# Power_Supply_board.net
KiCad netlist of a schematic drawn in EAGLE
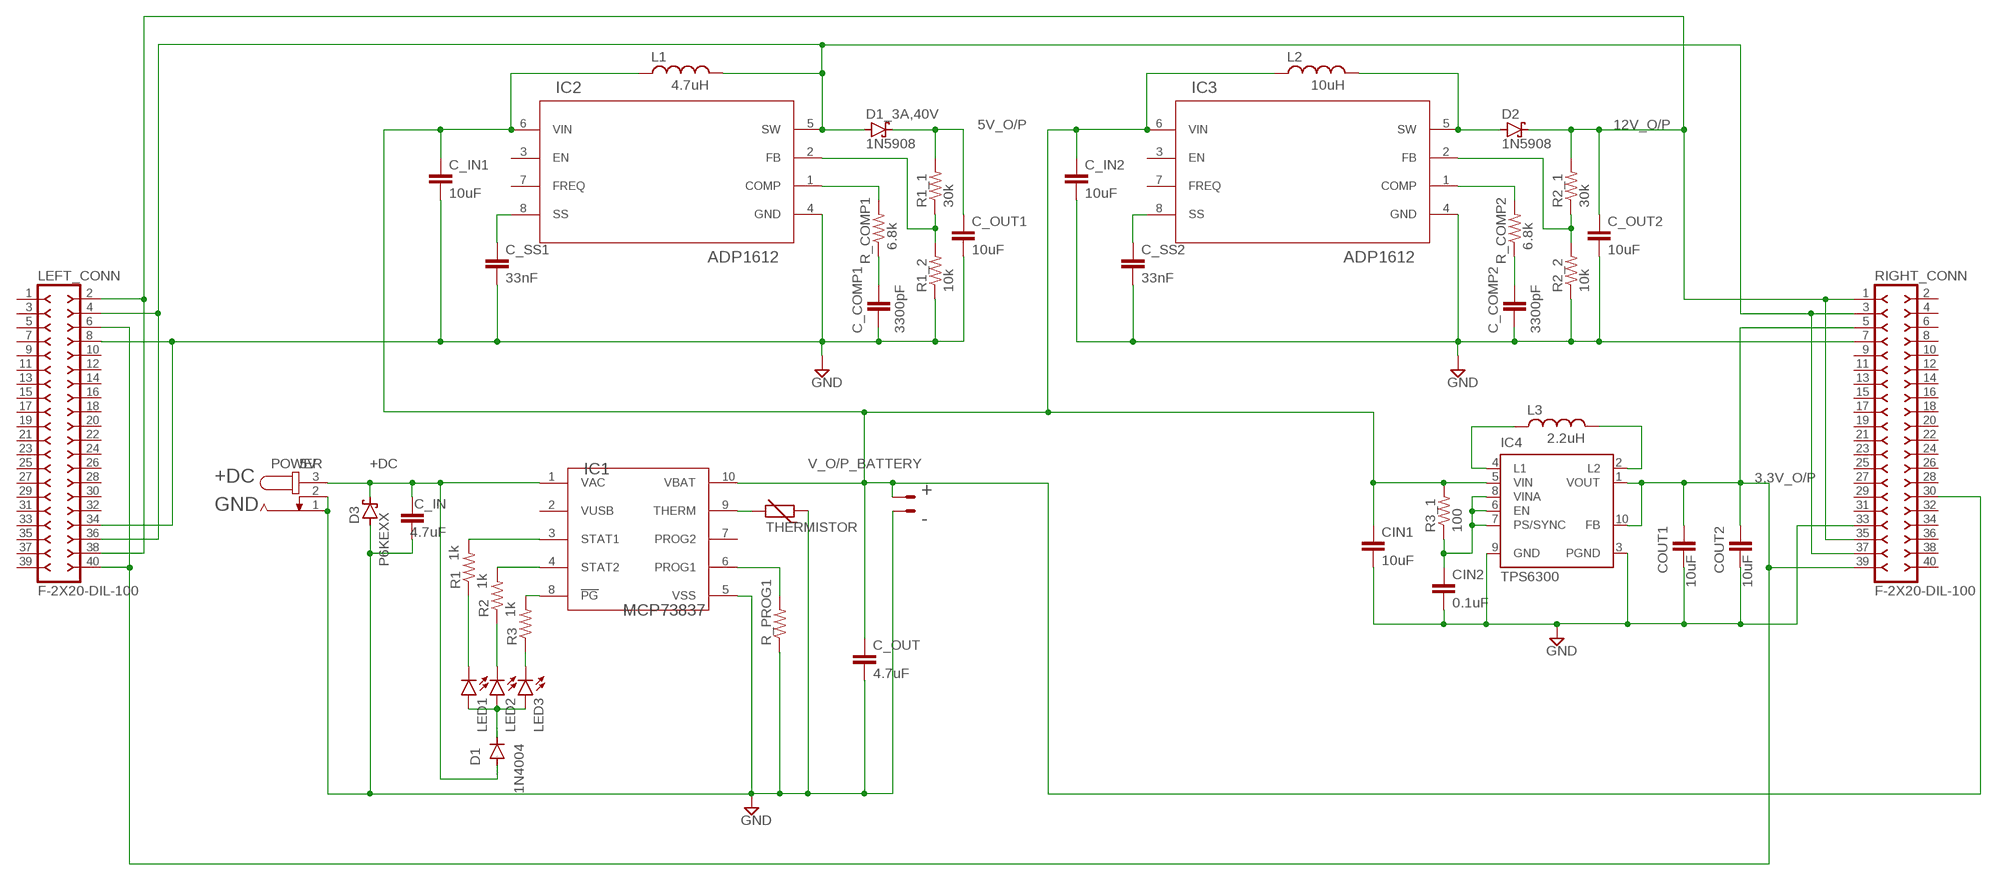
[diagram p0: schematic, sheet 1]

(export (version "E")
  (design (tool "Eeschema 10.0.6"))
  (components
    (comp (ref "BATT-CHARGING")
      (value "JST-XH-02-PIN-ROUND-PAD")
      (footprint "eagle-import:JST-XH-02-PACKAGE-ROUND-PAD")
      (libsource (lib "eagle-import") (part "JST-XH-02-PIN-ROUND-PAD"))
    )
    (comp (ref "CIN1")
      (value "10uF")
      (footprint "eagle-import:C025-024X044")
      (libsource (lib "eagle-import") (part "C-EU025-024X044"))
    )
    (comp (ref "CIN2")
      (value "0.1uF")
      (footprint "eagle-import:C025-024X044")
      (libsource (lib "eagle-import") (part "C-EU025-024X044"))
    )
    (comp (ref "COUT1")
      (value "10uF")
      (footprint "eagle-import:C025-024X044")
      (libsource (lib "eagle-import") (part "C-EU025-024X044"))
    )
    (comp (ref "COUT2")
      (value "10uF")
      (footprint "eagle-import:C025-024X044")
      (libsource (lib "eagle-import") (part "C-EU025-024X044"))
    )
    (comp (ref "C_COMP1")
      (value "3300pF")
      (footprint "eagle-import:C025-024X044")
      (libsource (lib "eagle-import") (part "C-EU025-024X044"))
    )
    (comp (ref "C_COMP2")
      (value "3300pF")
      (footprint "eagle-import:C025-024X044")
      (libsource (lib "eagle-import") (part "C-EU025-024X044"))
    )
    (comp (ref "C_IN")
      (value "4.7uF")
      (footprint "eagle-import:C025-024X044")
      (libsource (lib "eagle-import") (part "C-EU025-024X044"))
    )
    (comp (ref "C_IN1")
      (value "10uF")
      (footprint "eagle-import:C025-024X044")
      (libsource (lib "eagle-import") (part "C-EU025-024X044"))
    )
    (comp (ref "C_IN2")
      (value "10uF")
      (footprint "eagle-import:C025-024X044")
      (libsource (lib "eagle-import") (part "C-EU025-024X044"))
    )
    (comp (ref "C_OUT")
      (value "4.7uF")
      (footprint "eagle-import:C025-024X044")
      (libsource (lib "eagle-import") (part "C-EU025-024X044"))
    )
    (comp (ref "C_OUT1")
      (value "10uF")
      (footprint "eagle-import:C025-024X044")
      (libsource (lib "eagle-import") (part "C-EU025-024X044"))
    )
    (comp (ref "C_OUT2")
      (value "10uF")
      (footprint "eagle-import:C025-024X044")
      (libsource (lib "eagle-import") (part "C-EU025-024X044"))
    )
    (comp (ref "C_SS1")
      (value "33nF")
      (footprint "eagle-import:C025-024X044")
      (libsource (lib "eagle-import") (part "C-EU025-024X044"))
    )
    (comp (ref "C_SS2")
      (value "33nF")
      (footprint "eagle-import:C025-024X044")
      (libsource (lib "eagle-import") (part "C-EU025-024X044"))
    )
    (comp (ref "D1")
      (value "1N4004")
      (footprint "eagle-import:DO41-10")
      (libsource (lib "eagle-import") (part "1N4004"))
    )
    (comp (ref "D1_3A,40V")
      (value "1N5908")
      (footprint "eagle-import:C4111-15")
      (libsource (lib "eagle-import") (part "1N5908"))
    )
    (comp (ref "D2")
      (value "1N5908")
      (footprint "eagle-import:C4111-15")
      (libsource (lib "eagle-import") (part "1N5908"))
    )
    (comp (ref "D3")
      (value "P6KEXX")
      (footprint "eagle-import:CB417-15")
      (libsource (lib "eagle-import") (part "P6KEXX"))
    )
    (comp (ref "IC1")
      (value "MCP73837")
      (footprint "eagle-import:MSOP10_MC_MCH")
      (fields (field (name "MANUFACTURER_PART_NUMBER") "MCP73837-FCI/UN"))
      (libsource (lib "eagle-import") (part "MCP73837-FCI/UN"))
    )
    (comp (ref "IC2")
      (value "ADP1612")
      (footprint "eagle-import:RM_8_ADI")
      (fields (field (name "MANUFACTURER_PART_NUMBER") "ADP1612ARMZ-R7"))
      (libsource (lib "eagle-import") (part "ADP1612"))
    )
    (comp (ref "IC3")
      (value "ADP1612")
      (footprint "eagle-import:RM_8_ADI")
      (fields (field (name "MANUFACTURER_PART_NUMBER") "ADP1612ARMZ-R7"))
      (libsource (lib "eagle-import") (part "ADP1612"))
    )
    (comp (ref "IC4")
      (value "TPS6300")
      (footprint "eagle-import:DRC-S-PVSON-N10")
      (fields (field (name "MPN") "TPS63000DRCTG4"))
      (libsource (lib "eagle-import") (part "TPS6300"))
    )
    (comp (ref "L1")
      (value "4.7uH")
      (footprint "eagle-import:0204_7")
      (libsource (lib "eagle-import") (part "L-US0204/7"))
    )
    (comp (ref "L2")
      (value "10uH")
      (footprint "eagle-import:0204_7")
      (libsource (lib "eagle-import") (part "L-US0204/7"))
    )
    (comp (ref "L3")
      (value "2.2uH")
      (footprint "eagle-import:0204_7")
      (libsource (lib "eagle-import") (part "L-US0204/7"))
    )
    (comp (ref "LED1")
      (value "LED3MM")
      (footprint "eagle-import:LED3MM")
      (libsource (lib "eagle-import") (part "LED3MM"))
    )
    (comp (ref "LED2")
      (value "LED3MM")
      (footprint "eagle-import:LED3MM")
      (libsource (lib "eagle-import") (part "LED3MM"))
    )
    (comp (ref "LED3")
      (value "LED3MM")
      (footprint "eagle-import:LED3MM")
      (libsource (lib "eagle-import") (part "LED3MM"))
    )
    (comp (ref "LEFT_CONN")
      (value "F-2X20-DIL-100")
      (footprint "eagle-import:DIL-100-2X20")
      (libsource (lib "eagle-import") (part "F-2X20-DIL-100"))
    )
    (comp (ref "POWER")
      (value "5V")
      (footprint "eagle-import:SPC4077")
      (libsource (lib "eagle-import") (part "JACK-PLUG0"))
    )
    (comp (ref "R1")
      (value "1k")
      (footprint "eagle-import:0204_7")
      (libsource (lib "eagle-import") (part "R-US_0204/7"))
    )
    (comp (ref "R1_1")
      (value "30k")
      (footprint "eagle-import:0204_7")
      (libsource (lib "eagle-import") (part "R-US_0204/7"))
    )
    (comp (ref "R1_2")
      (value "10k")
      (footprint "eagle-import:0204_7")
      (libsource (lib "eagle-import") (part "R-US_0204/7"))
    )
    (comp (ref "R2")
      (value "1k")
      (footprint "eagle-import:0204_7")
      (libsource (lib "eagle-import") (part "R-US_0204/7"))
    )
    (comp (ref "R2_1")
      (value "30k")
      (footprint "eagle-import:0204_7")
      (libsource (lib "eagle-import") (part "R-US_0204/7"))
    )
    (comp (ref "R2_2")
      (value "10k")
      (footprint "eagle-import:0204_7")
      (libsource (lib "eagle-import") (part "R-US_0204/7"))
    )
    (comp (ref "R3")
      (value "1k")
      (footprint "eagle-import:0204_7")
      (libsource (lib "eagle-import") (part "R-US_0204/7"))
    )
    (comp (ref "R3_1")
      (value "100")
      (footprint "eagle-import:0204_7")
      (libsource (lib "eagle-import") (part "R-US_0204/7"))
    )
    (comp (ref "RIGHT_CONN")
      (value "F-2X20-DIL-100")
      (footprint "eagle-import:DIL-100-2X20")
      (libsource (lib "eagle-import") (part "F-2X20-DIL-100"))
    )
    (comp (ref "R_COMP1")
      (value "6.8k")
      (footprint "eagle-import:0204_7")
      (libsource (lib "eagle-import") (part "R-US_0204/7"))
    )
    (comp (ref "R_COMP2")
      (value "6.8k")
      (footprint "eagle-import:0204_7")
      (libsource (lib "eagle-import") (part "R-US_0204/7"))
    )
    (comp (ref "R_PROG1")
      (value "R-US_0204/7")
      (footprint "eagle-import:0204_7")
      (libsource (lib "eagle-import") (part "R-US_0204/7"))
    )
    (comp (ref "THERMISTOR")
      (value "THERMISTOR-5")
      (footprint "eagle-import:R-5")
      (libsource (lib "eagle-import") (part "THERMISTOR-5"))
    )
  )
  (nets
    (net (code "1") (name "/+DC") (class "Default")
      (node (ref "C_IN") (pin "1") (pinfunction "1_1") (pintype "passive"))
      (node (ref "D1") (pin "A") (pinfunction "A_A") (pintype "passive"))
      (node (ref "D3") (pin "C") (pinfunction "C_C") (pintype "passive"))
      (node (ref "IC1") (pin "1") (pinfunction "VAC_1") (pintype "passive"))
      (node (ref "POWER") (pin "3") (pinfunction "3_3") (pintype "passive"))
    )
    (net (code "2") (name "/3.3V_O{slash}P") (class "Default")
      (node (ref "COUT1") (pin "1") (pinfunction "1_1") (pintype "passive"))
      (node (ref "COUT2") (pin "1") (pinfunction "1_1") (pintype "passive"))
      (node (ref "IC4") (pin "1") (pinfunction "VOUT_1") (pintype "output"))
      (node (ref "IC4") (pin "10") (pinfunction "FB_10") (pintype "input"))
      (node (ref "LEFT_CONN") (pin "40") (pinfunction "40_40") (pintype "passive"))
      (node (ref "LEFT_CONN") (pin "6") (pinfunction "6_6") (pintype "passive"))
      (node (ref "RIGHT_CONN") (pin "39") (pinfunction "39_39") (pintype "passive"))
      (node (ref "RIGHT_CONN") (pin "5") (pinfunction "5_5") (pintype "passive"))
    )
    (net (code "3") (name "/5V_O{slash}P") (class "Default")
      (node (ref "C_OUT1") (pin "1") (pinfunction "1_1") (pintype "passive"))
      (node (ref "D1_3A,40V") (pin "C") (pinfunction "C_C") (pintype "passive"))
      (node (ref "R1_1") (pin "2") (pinfunction "2_2") (pintype "passive"))
    )
    (net (code "4") (name "/12V_O{slash}P") (class "Default")
      (node (ref "C_OUT2") (pin "1") (pinfunction "1_1") (pintype "passive"))
      (node (ref "D2") (pin "C") (pinfunction "C_C") (pintype "passive"))
      (node (ref "LEFT_CONN") (pin "2") (pinfunction "2_2") (pintype "passive"))
      (node (ref "LEFT_CONN") (pin "38") (pinfunction "38_38") (pintype "passive"))
      (node (ref "R2_1") (pin "2") (pinfunction "2_2") (pintype "passive"))
      (node (ref "RIGHT_CONN") (pin "1") (pinfunction "1_1") (pintype "passive"))
      (node (ref "RIGHT_CONN") (pin "35") (pinfunction "35_35") (pintype "passive"))
    )
    (net (code "5") (name "/V_O{slash}P_BATTERY") (class "Default")
      (node (ref "BATT-CHARGING") (pin "1") (pinfunction "S_1") (pintype "passive"))
      (node (ref "CIN1") (pin "1") (pinfunction "1_1") (pintype "passive"))
      (node (ref "C_IN1") (pin "1") (pinfunction "1_1") (pintype "passive"))
      (node (ref "C_IN2") (pin "1") (pinfunction "1_1") (pintype "passive"))
      (node (ref "C_OUT") (pin "1") (pinfunction "1_1") (pintype "passive"))
      (node (ref "IC1") (pin "10") (pinfunction "VBAT_10") (pintype "passive"))
      (node (ref "IC2") (pin "6") (pinfunction "VIN_6") (pintype "passive"))
      (node (ref "IC3") (pin "6") (pinfunction "VIN_6") (pintype "passive"))
      (node (ref "IC4") (pin "5") (pinfunction "VIN_5") (pintype "input"))
      (node (ref "L1") (pin "1") (pinfunction "1_1") (pintype "passive"))
      (node (ref "L2") (pin "1") (pinfunction "1_1") (pintype "passive"))
      (node (ref "R3_1") (pin "2") (pinfunction "2_2") (pintype "passive"))
      (node (ref "RIGHT_CONN") (pin "30") (pinfunction "30_30") (pintype "passive"))
    )
    (net (code "6") (name "GND") (class "Default")
      (node (ref "BATT-CHARGING") (pin "2") (pinfunction "S_2") (pintype "passive"))
      (node (ref "CIN1") (pin "2") (pinfunction "2_2") (pintype "passive"))
      (node (ref "CIN2") (pin "2") (pinfunction "2_2") (pintype "passive"))
      (node (ref "COUT1") (pin "2") (pinfunction "2_2") (pintype "passive"))
      (node (ref "COUT2") (pin "2") (pinfunction "2_2") (pintype "passive"))
      (node (ref "C_COMP1") (pin "2") (pinfunction "2_2") (pintype "passive"))
      (node (ref "C_COMP2") (pin "2") (pinfunction "2_2") (pintype "passive"))
      (node (ref "C_IN") (pin "2") (pinfunction "2_2") (pintype "passive"))
      (node (ref "C_IN1") (pin "2") (pinfunction "2_2") (pintype "passive"))
      (node (ref "C_IN2") (pin "2") (pinfunction "2_2") (pintype "passive"))
      (node (ref "C_OUT") (pin "2") (pinfunction "2_2") (pintype "passive"))
      (node (ref "C_OUT1") (pin "2") (pinfunction "2_2") (pintype "passive"))
      (node (ref "C_OUT2") (pin "2") (pinfunction "2_2") (pintype "passive"))
      (node (ref "C_SS1") (pin "2") (pinfunction "2_2") (pintype "passive"))
      (node (ref "C_SS2") (pin "2") (pinfunction "2_2") (pintype "passive"))
      (node (ref "D3") (pin "A") (pinfunction "A_A") (pintype "passive"))
      (node (ref "IC1") (pin "5") (pinfunction "VSS_5") (pintype "passive"))
      (node (ref "IC2") (pin "4") (pinfunction "GND_4") (pintype "passive"))
      (node (ref "IC3") (pin "4") (pinfunction "GND_4") (pintype "passive"))
      (node (ref "IC4") (pin "3") (pinfunction "PGND_3") (pintype "power_in"))
      (node (ref "IC4") (pin "9") (pinfunction "GND_9") (pintype "power_in"))
      (node (ref "LEFT_CONN") (pin "34") (pinfunction "34_34") (pintype "passive"))
      (node (ref "LEFT_CONN") (pin "8") (pinfunction "8_8") (pintype "passive"))
      (node (ref "POWER") (pin "1") (pinfunction "1_1") (pintype "passive"))
      (node (ref "POWER") (pin "2") (pinfunction "2_2") (pintype "passive"))
      (node (ref "R1_2") (pin "1") (pinfunction "1_1") (pintype "passive"))
      (node (ref "R2_2") (pin "1") (pinfunction "1_1") (pintype "passive"))
      (node (ref "RIGHT_CONN") (pin "33") (pinfunction "33_33") (pintype "passive"))
      (node (ref "RIGHT_CONN") (pin "7") (pinfunction "7_7") (pintype "passive"))
      (node (ref "R_PROG1") (pin "1") (pinfunction "1_1") (pintype "passive"))
      (node (ref "THERMISTOR") (pin "1") (pinfunction "1_1") (pintype "passive"))
    )
    (net (code "7") (name "Net-(C_COMP1-Pad1)") (class "Default")
      (node (ref "C_COMP1") (pin "1") (pinfunction "1_1") (pintype "passive"))
      (node (ref "R_COMP1") (pin "1") (pinfunction "1_1") (pintype "passive"))
    )
    (net (code "8") (name "Net-(C_COMP2-Pad1)") (class "Default")
      (node (ref "C_COMP2") (pin "1") (pinfunction "1_1") (pintype "passive"))
      (node (ref "R_COMP2") (pin "1") (pinfunction "1_1") (pintype "passive"))
    )
    (net (code "9") (name "Net-(D1-PadC)") (class "Default")
      (node (ref "D1") (pin "C") (pinfunction "C_C") (pintype "passive"))
      (node (ref "LED1") (pin "A") (pinfunction "A_A") (pintype "passive"))
      (node (ref "LED2") (pin "A") (pinfunction "A_A") (pintype "passive"))
      (node (ref "LED3") (pin "A") (pinfunction "A_A") (pintype "passive"))
    )
    (net (code "10") (name "Net-(IC1-PROG1)") (class "Default")
      (node (ref "IC1") (pin "6") (pinfunction "PROG1_6") (pintype "passive"))
      (node (ref "R_PROG1") (pin "2") (pinfunction "2_2") (pintype "passive"))
    )
    (net (code "11") (name "Net-(IC1-STAT1)") (class "Default")
      (node (ref "IC1") (pin "3") (pinfunction "STAT1_3") (pintype "passive"))
      (node (ref "R1") (pin "2") (pinfunction "2_2") (pintype "passive"))
    )
    (net (code "12") (name "Net-(IC1-STAT2)") (class "Default")
      (node (ref "IC1") (pin "4") (pinfunction "STAT2_4") (pintype "passive"))
      (node (ref "R2") (pin "2") (pinfunction "2_2") (pintype "passive"))
    )
    (net (code "13") (name "Net-(IC1-THERM)") (class "Default")
      (node (ref "IC1") (pin "9") (pinfunction "THERM_9") (pintype "passive"))
      (node (ref "THERMISTOR") (pin "2") (pinfunction "2_2") (pintype "passive"))
    )
    (net (code "14") (name "Net-(IC1-~{PG})") (class "Default")
      (node (ref "IC1") (pin "8") (pinfunction "~{PG}_8") (pintype "passive"))
      (node (ref "R3") (pin "2") (pinfunction "2_2") (pintype "passive"))
    )
    (net (code "15") (name "Net-(IC2-COMP)") (class "Default")
      (node (ref "IC2") (pin "1") (pinfunction "COMP_1") (pintype "passive"))
      (node (ref "R_COMP1") (pin "2") (pinfunction "2_2") (pintype "passive"))
    )
    (net (code "16") (name "Net-(IC2-FB)") (class "Default")
      (node (ref "IC2") (pin "2") (pinfunction "FB_2") (pintype "passive"))
      (node (ref "R1_1") (pin "1") (pinfunction "1_1") (pintype "passive"))
      (node (ref "R1_2") (pin "2") (pinfunction "2_2") (pintype "passive"))
    )
    (net (code "17") (name "Net-(IC2-SS)") (class "Default")
      (node (ref "C_SS1") (pin "1") (pinfunction "1_1") (pintype "passive"))
      (node (ref "IC2") (pin "8") (pinfunction "SS_8") (pintype "passive"))
    )
    (net (code "18") (name "Net-(IC2-SW)") (class "Default")
      (node (ref "D1_3A,40V") (pin "A") (pinfunction "A_A") (pintype "passive"))
      (node (ref "IC2") (pin "5") (pinfunction "SW_5") (pintype "passive"))
      (node (ref "L1") (pin "2") (pinfunction "2_2") (pintype "passive"))
      (node (ref "LEFT_CONN") (pin "36") (pinfunction "36_36") (pintype "passive"))
      (node (ref "LEFT_CONN") (pin "4") (pinfunction "4_4") (pintype "passive"))
      (node (ref "RIGHT_CONN") (pin "3") (pinfunction "3_3") (pintype "passive"))
      (node (ref "RIGHT_CONN") (pin "37") (pinfunction "37_37") (pintype "passive"))
    )
    (net (code "19") (name "Net-(IC3-COMP)") (class "Default")
      (node (ref "IC3") (pin "1") (pinfunction "COMP_1") (pintype "passive"))
      (node (ref "R_COMP2") (pin "2") (pinfunction "2_2") (pintype "passive"))
    )
    (net (code "20") (name "Net-(IC3-FB)") (class "Default")
      (node (ref "IC3") (pin "2") (pinfunction "FB_2") (pintype "passive"))
      (node (ref "R2_1") (pin "1") (pinfunction "1_1") (pintype "passive"))
      (node (ref "R2_2") (pin "2") (pinfunction "2_2") (pintype "passive"))
    )
    (net (code "21") (name "Net-(IC3-SS)") (class "Default")
      (node (ref "C_SS2") (pin "1") (pinfunction "1_1") (pintype "passive"))
      (node (ref "IC3") (pin "8") (pinfunction "SS_8") (pintype "passive"))
    )
    (net (code "22") (name "Net-(IC3-SW)") (class "Default")
      (node (ref "D2") (pin "A") (pinfunction "A_A") (pintype "passive"))
      (node (ref "IC3") (pin "5") (pinfunction "SW_5") (pintype "passive"))
      (node (ref "L2") (pin "2") (pinfunction "2_2") (pintype "passive"))
    )
    (net (code "23") (name "Net-(IC4A-EN)") (class "Default")
      (node (ref "CIN2") (pin "1") (pinfunction "1_1") (pintype "passive"))
      (node (ref "IC4") (pin "6") (pinfunction "EN_6") (pintype "input"))
      (node (ref "IC4") (pin "7") (pinfunction "PS/SYNC_7") (pintype "input"))
      (node (ref "IC4") (pin "8") (pinfunction "VINA_8") (pintype "input"))
      (node (ref "R3_1") (pin "1") (pinfunction "1_1") (pintype "passive"))
    )
    (net (code "24") (name "Net-(IC4A-L1)") (class "Default")
      (node (ref "IC4") (pin "4") (pinfunction "L1_4") (pintype "passive"))
      (node (ref "L3") (pin "1") (pinfunction "1_1") (pintype "passive"))
    )
    (net (code "25") (name "Net-(IC4A-L2)") (class "Default")
      (node (ref "IC4") (pin "2") (pinfunction "L2_2") (pintype "passive"))
      (node (ref "L3") (pin "2") (pinfunction "2_2") (pintype "passive"))
    )
    (net (code "26") (name "Net-(LED1-C)") (class "Default")
      (node (ref "LED1") (pin "K") (pinfunction "C_K") (pintype "passive"))
      (node (ref "R1") (pin "1") (pinfunction "1_1") (pintype "passive"))
    )
    (net (code "27") (name "Net-(LED2-C)") (class "Default")
      (node (ref "LED2") (pin "K") (pinfunction "C_K") (pintype "passive"))
      (node (ref "R2") (pin "1") (pinfunction "1_1") (pintype "passive"))
    )
    (net (code "28") (name "Net-(LED3-C)") (class "Default")
      (node (ref "LED3") (pin "K") (pinfunction "C_K") (pintype "passive"))
      (node (ref "R3") (pin "1") (pinfunction "1_1") (pintype "passive"))
    )
    (net (code "29") (name "unconnected-(IC1-PROG2-Pad7)") (class "Default")
      (node (ref "IC1") (pin "7") (pinfunction "PROG2_7") (pintype "passive"))
    )
    (net (code "30") (name "unconnected-(IC1-VUSB-Pad2)") (class "Default")
      (node (ref "IC1") (pin "2") (pinfunction "VUSB_2") (pintype "passive"))
    )
    (net (code "31") (name "unconnected-(IC2-EN-Pad3)") (class "Default")
      (node (ref "IC2") (pin "3") (pinfunction "EN_3") (pintype "passive"))
    )
    (net (code "32") (name "unconnected-(IC2-FREQ-Pad7)") (class "Default")
      (node (ref "IC2") (pin "7") (pinfunction "FREQ_7") (pintype "passive"))
    )
    (net (code "33") (name "unconnected-(IC3-EN-Pad3)") (class "Default")
      (node (ref "IC3") (pin "3") (pinfunction "EN_3") (pintype "passive"))
    )
    (net (code "34") (name "unconnected-(IC3-FREQ-Pad7)") (class "Default")
      (node (ref "IC3") (pin "7") (pinfunction "FREQ_7") (pintype "passive"))
    )
    (net (code "35") (name "unconnected-(LEFT_CONN-Pad1)") (class "Default")
      (node (ref "LEFT_CONN") (pin "1") (pinfunction "1_1") (pintype "passive"))
    )
    (net (code "36") (name "unconnected-(LEFT_CONN-Pad3)") (class "Default")
      (node (ref "LEFT_CONN") (pin "3") (pinfunction "3_3") (pintype "passive"))
    )
    (net (code "37") (name "unconnected-(LEFT_CONN-Pad5)") (class "Default")
      (node (ref "LEFT_CONN") (pin "5") (pinfunction "5_5") (pintype "passive"))
    )
    (net (code "38") (name "unconnected-(LEFT_CONN-Pad7)") (class "Default")
      (node (ref "LEFT_CONN") (pin "7") (pinfunction "7_7") (pintype "passive"))
    )
    (net (code "39") (name "unconnected-(LEFT_CONN-Pad9)") (class "Default")
      (node (ref "LEFT_CONN") (pin "9") (pinfunction "9_9") (pintype "passive"))
    )
    (net (code "40") (name "unconnected-(LEFT_CONN-Pad10)") (class "Default")
      (node (ref "LEFT_CONN") (pin "10") (pinfunction "10_10") (pintype "passive"))
    )
    (net (code "41") (name "unconnected-(LEFT_CONN-Pad11)") (class "Default")
      (node (ref "LEFT_CONN") (pin "11") (pinfunction "11_11") (pintype "passive"))
    )
    (net (code "42") (name "unconnected-(LEFT_CONN-Pad12)") (class "Default")
      (node (ref "LEFT_CONN") (pin "12") (pinfunction "12_12") (pintype "passive"))
    )
    (net (code "43") (name "unconnected-(LEFT_CONN-Pad13)") (class "Default")
      (node (ref "LEFT_CONN") (pin "13") (pinfunction "13_13") (pintype "passive"))
    )
    (net (code "44") (name "unconnected-(LEFT_CONN-Pad14)") (class "Default")
      (node (ref "LEFT_CONN") (pin "14") (pinfunction "14_14") (pintype "passive"))
    )
    (net (code "45") (name "unconnected-(LEFT_CONN-Pad15)") (class "Default")
      (node (ref "LEFT_CONN") (pin "15") (pinfunction "15_15") (pintype "passive"))
    )
    (net (code "46") (name "unconnected-(LEFT_CONN-Pad16)") (class "Default")
      (node (ref "LEFT_CONN") (pin "16") (pinfunction "16_16") (pintype "passive"))
    )
    (net (code "47") (name "unconnected-(LEFT_CONN-Pad17)") (class "Default")
      (node (ref "LEFT_CONN") (pin "17") (pinfunction "17_17") (pintype "passive"))
    )
    (net (code "48") (name "unconnected-(LEFT_CONN-Pad18)") (class "Default")
      (node (ref "LEFT_CONN") (pin "18") (pinfunction "18_18") (pintype "passive"))
    )
    (net (code "49") (name "unconnected-(LEFT_CONN-Pad19)") (class "Default")
      (node (ref "LEFT_CONN") (pin "19") (pinfunction "19_19") (pintype "passive"))
    )
    (net (code "50") (name "unconnected-(LEFT_CONN-Pad20)") (class "Default")
      (node (ref "LEFT_CONN") (pin "20") (pinfunction "20_20") (pintype "passive"))
    )
    (net (code "51") (name "unconnected-(LEFT_CONN-Pad21)") (class "Default")
      (node (ref "LEFT_CONN") (pin "21") (pinfunction "21_21") (pintype "passive"))
    )
    (net (code "52") (name "unconnected-(LEFT_CONN-Pad22)") (class "Default")
      (node (ref "LEFT_CONN") (pin "22") (pinfunction "22_22") (pintype "passive"))
    )
    (net (code "53") (name "unconnected-(LEFT_CONN-Pad23)") (class "Default")
      (node (ref "LEFT_CONN") (pin "23") (pinfunction "23_23") (pintype "passive"))
    )
    (net (code "54") (name "unconnected-(LEFT_CONN-Pad24)") (class "Default")
      (node (ref "LEFT_CONN") (pin "24") (pinfunction "24_24") (pintype "passive"))
    )
    (net (code "55") (name "unconnected-(LEFT_CONN-Pad25)") (class "Default")
      (node (ref "LEFT_CONN") (pin "25") (pinfunction "25_25") (pintype "passive"))
    )
    (net (code "56") (name "unconnected-(LEFT_CONN-Pad26)") (class "Default")
      (node (ref "LEFT_CONN") (pin "26") (pinfunction "26_26") (pintype "passive"))
    )
    (net (code "57") (name "unconnected-(LEFT_CONN-Pad27)") (class "Default")
      (node (ref "LEFT_CONN") (pin "27") (pinfunction "27_27") (pintype "passive"))
    )
    (net (code "58") (name "unconnected-(LEFT_CONN-Pad28)") (class "Default")
      (node (ref "LEFT_CONN") (pin "28") (pinfunction "28_28") (pintype "passive"))
    )
    (net (code "59") (name "unconnected-(LEFT_CONN-Pad29)") (class "Default")
      (node (ref "LEFT_CONN") (pin "29") (pinfunction "29_29") (pintype "passive"))
    )
    (net (code "60") (name "unconnected-(LEFT_CONN-Pad30)") (class "Default")
      (node (ref "LEFT_CONN") (pin "30") (pinfunction "30_30") (pintype "passive"))
    )
    (net (code "61") (name "unconnected-(LEFT_CONN-Pad31)") (class "Default")
      (node (ref "LEFT_CONN") (pin "31") (pinfunction "31_31") (pintype "passive"))
    )
    (net (code "62") (name "unconnected-(LEFT_CONN-Pad32)") (class "Default")
      (node (ref "LEFT_CONN") (pin "32") (pinfunction "32_32") (pintype "passive"))
    )
    (net (code "63") (name "unconnected-(LEFT_CONN-Pad33)") (class "Default")
      (node (ref "LEFT_CONN") (pin "33") (pinfunction "33_33") (pintype "passive"))
    )
    (net (code "64") (name "unconnected-(LEFT_CONN-Pad35)") (class "Default")
      (node (ref "LEFT_CONN") (pin "35") (pinfunction "35_35") (pintype "passive"))
    )
    (net (code "65") (name "unconnected-(LEFT_CONN-Pad37)") (class "Default")
      (node (ref "LEFT_CONN") (pin "37") (pinfunction "37_37") (pintype "passive"))
    )
    (net (code "66") (name "unconnected-(LEFT_CONN-Pad39)") (class "Default")
      (node (ref "LEFT_CONN") (pin "39") (pinfunction "39_39") (pintype "passive"))
    )
    (net (code "67") (name "unconnected-(RIGHT_CONN-Pad2)") (class "Default")
      (node (ref "RIGHT_CONN") (pin "2") (pinfunction "2_2") (pintype "passive"))
    )
    (net (code "68") (name "unconnected-(RIGHT_CONN-Pad4)") (class "Default")
      (node (ref "RIGHT_CONN") (pin "4") (pinfunction "4_4") (pintype "passive"))
    )
    (net (code "69") (name "unconnected-(RIGHT_CONN-Pad6)") (class "Default")
      (node (ref "RIGHT_CONN") (pin "6") (pinfunction "6_6") (pintype "passive"))
    )
    (net (code "70") (name "unconnected-(RIGHT_CONN-Pad8)") (class "Default")
      (node (ref "RIGHT_CONN") (pin "8") (pinfunction "8_8") (pintype "passive"))
    )
    (net (code "71") (name "unconnected-(RIGHT_CONN-Pad9)") (class "Default")
      (node (ref "RIGHT_CONN") (pin "9") (pinfunction "9_9") (pintype "passive"))
    )
    (net (code "72") (name "unconnected-(RIGHT_CONN-Pad10)") (class "Default")
      (node (ref "RIGHT_CONN") (pin "10") (pinfunction "10_10") (pintype "passive"))
    )
    (net (code "73") (name "unconnected-(RIGHT_CONN-Pad11)") (class "Default")
      (node (ref "RIGHT_CONN") (pin "11") (pinfunction "11_11") (pintype "passive"))
    )
    (net (code "74") (name "unconnected-(RIGHT_CONN-Pad12)") (class "Default")
      (node (ref "RIGHT_CONN") (pin "12") (pinfunction "12_12") (pintype "passive"))
    )
    (net (code "75") (name "unconnected-(RIGHT_CONN-Pad13)") (class "Default")
      (node (ref "RIGHT_CONN") (pin "13") (pinfunction "13_13") (pintype "passive"))
    )
    (net (code "76") (name "unconnected-(RIGHT_CONN-Pad14)") (class "Default")
      (node (ref "RIGHT_CONN") (pin "14") (pinfunction "14_14") (pintype "passive"))
    )
    (net (code "77") (name "unconnected-(RIGHT_CONN-Pad15)") (class "Default")
      (node (ref "RIGHT_CONN") (pin "15") (pinfunction "15_15") (pintype "passive"))
    )
    (net (code "78") (name "unconnected-(RIGHT_CONN-Pad16)") (class "Default")
      (node (ref "RIGHT_CONN") (pin "16") (pinfunction "16_16") (pintype "passive"))
    )
    (net (code "79") (name "unconnected-(RIGHT_CONN-Pad17)") (class "Default")
      (node (ref "RIGHT_CONN") (pin "17") (pinfunction "17_17") (pintype "passive"))
    )
    (net (code "80") (name "unconnected-(RIGHT_CONN-Pad18)") (class "Default")
      (node (ref "RIGHT_CONN") (pin "18") (pinfunction "18_18") (pintype "passive"))
    )
    (net (code "81") (name "unconnected-(RIGHT_CONN-Pad19)") (class "Default")
      (node (ref "RIGHT_CONN") (pin "19") (pinfunction "19_19") (pintype "passive"))
    )
    (net (code "82") (name "unconnected-(RIGHT_CONN-Pad20)") (class "Default")
      (node (ref "RIGHT_CONN") (pin "20") (pinfunction "20_20") (pintype "passive"))
    )
    (net (code "83") (name "unconnected-(RIGHT_CONN-Pad21)") (class "Default")
      (node (ref "RIGHT_CONN") (pin "21") (pinfunction "21_21") (pintype "passive"))
    )
    (net (code "84") (name "unconnected-(RIGHT_CONN-Pad22)") (class "Default")
      (node (ref "RIGHT_CONN") (pin "22") (pinfunction "22_22") (pintype "passive"))
    )
    (net (code "85") (name "unconnected-(RIGHT_CONN-Pad23)") (class "Default")
      (node (ref "RIGHT_CONN") (pin "23") (pinfunction "23_23") (pintype "passive"))
    )
    (net (code "86") (name "unconnected-(RIGHT_CONN-Pad24)") (class "Default")
      (node (ref "RIGHT_CONN") (pin "24") (pinfunction "24_24") (pintype "passive"))
    )
    (net (code "87") (name "unconnected-(RIGHT_CONN-Pad25)") (class "Default")
      (node (ref "RIGHT_CONN") (pin "25") (pinfunction "25_25") (pintype "passive"))
    )
    (net (code "88") (name "unconnected-(RIGHT_CONN-Pad26)") (class "Default")
      (node (ref "RIGHT_CONN") (pin "26") (pinfunction "26_26") (pintype "passive"))
    )
    (net (code "89") (name "unconnected-(RIGHT_CONN-Pad27)") (class "Default")
      (node (ref "RIGHT_CONN") (pin "27") (pinfunction "27_27") (pintype "passive"))
    )
    (net (code "90") (name "unconnected-(RIGHT_CONN-Pad28)") (class "Default")
      (node (ref "RIGHT_CONN") (pin "28") (pinfunction "28_28") (pintype "passive"))
    )
    (net (code "91") (name "unconnected-(RIGHT_CONN-Pad29)") (class "Default")
      (node (ref "RIGHT_CONN") (pin "29") (pinfunction "29_29") (pintype "passive"))
    )
    (net (code "92") (name "unconnected-(RIGHT_CONN-Pad31)") (class "Default")
      (node (ref "RIGHT_CONN") (pin "31") (pinfunction "31_31") (pintype "passive"))
    )
    (net (code "93") (name "unconnected-(RIGHT_CONN-Pad32)") (class "Default")
      (node (ref "RIGHT_CONN") (pin "32") (pinfunction "32_32") (pintype "passive"))
    )
    (net (code "94") (name "unconnected-(RIGHT_CONN-Pad34)") (class "Default")
      (node (ref "RIGHT_CONN") (pin "34") (pinfunction "34_34") (pintype "passive"))
    )
    (net (code "95") (name "unconnected-(RIGHT_CONN-Pad36)") (class "Default")
      (node (ref "RIGHT_CONN") (pin "36") (pinfunction "36_36") (pintype "passive"))
    )
    (net (code "96") (name "unconnected-(RIGHT_CONN-Pad38)") (class "Default")
      (node (ref "RIGHT_CONN") (pin "38") (pinfunction "38_38") (pintype "passive"))
    )
    (net (code "97") (name "unconnected-(RIGHT_CONN-Pad40)") (class "Default")
      (node (ref "RIGHT_CONN") (pin "40") (pinfunction "40_40") (pintype "passive"))
    )
  )
)
